# HoloCubicConnectV02_220109.net
KiCad netlist of a schematic drawn in Altium Designer
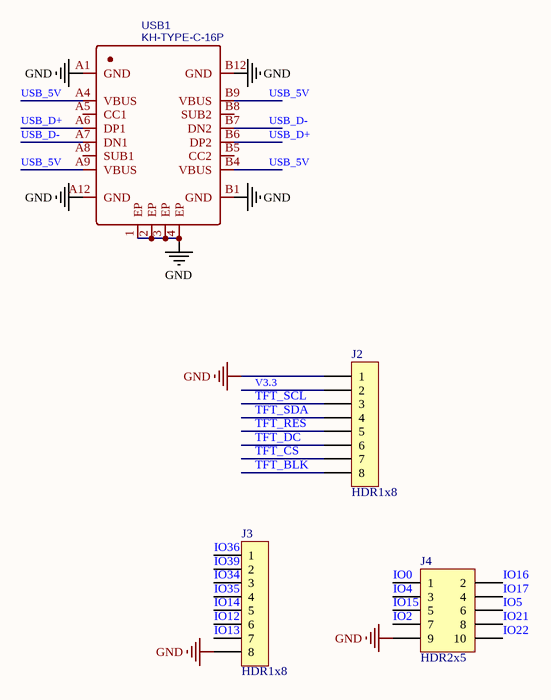
[diagram p0: HoloCubicConnectV02_220109.SchDoc]

(export (version "E")
  (design (tool "Eeschema 10.0.6"))
  (components
    (comp (ref "J2")
      (value "HDR1x8")
      (footprint "PIN-8-2.54-1.0")
      (description "Connector")
      (libsource (lib "General") (part "HDR1x8"))
    )
    (comp (ref "J3")
      (value "HDR1x8")
      (footprint "PIN-8-2.54-1.0")
      (description "Connector")
      (libsource (lib "General") (part "HDR1x8"))
    )
    (comp (ref "J4")
      (value "HDR2x5")
      (footprint "PIN-2x5-2.54-1.0")
      (description "Connector")
      (libsource (lib "General") (part "HDR2x5"))
    )
    (comp (ref "USB1")
      (value "KH-TYPE-C-16P")
      (footprint "USB-C-SMD_KH-TYPE-C-16P")
      (fields (field (name "BOM_SUPPLIER PART") "C709357") (field (name "CONTRIBUTOR") "LCSC"))
      (libsource (lib "altium-import") (part "root_0_KH-TYPE-C-16P_"))
    )
  )
  (nets
    (net (code "1") (name "/IO0") (class "Default")
      (node (ref "J4") (pin "1") (pinfunction "1_1") (pintype "passive"))
    )
    (net (code "2") (name "/IO2") (class "Default")
      (node (ref "J4") (pin "7") (pinfunction "7_7") (pintype "passive"))
    )
    (net (code "3") (name "/IO4") (class "Default")
      (node (ref "J4") (pin "3") (pinfunction "3_3") (pintype "passive"))
    )
    (net (code "4") (name "/IO5") (class "Default")
      (node (ref "J4") (pin "6") (pinfunction "6_6") (pintype "passive"))
    )
    (net (code "5") (name "/IO12") (class "Default")
      (node (ref "J3") (pin "6") (pinfunction "6_6") (pintype "passive"))
    )
    (net (code "6") (name "/IO13") (class "Default")
      (node (ref "J3") (pin "7") (pinfunction "7_7") (pintype "passive"))
    )
    (net (code "7") (name "/IO14") (class "Default")
      (node (ref "J3") (pin "5") (pinfunction "5_5") (pintype "passive"))
    )
    (net (code "8") (name "/IO15") (class "Default")
      (node (ref "J4") (pin "5") (pinfunction "5_5") (pintype "passive"))
    )
    (net (code "9") (name "/IO16") (class "Default")
      (node (ref "J4") (pin "2") (pinfunction "2_2") (pintype "passive"))
    )
    (net (code "10") (name "/IO17") (class "Default")
      (node (ref "J4") (pin "4") (pinfunction "4_4") (pintype "passive"))
    )
    (net (code "11") (name "/IO21") (class "Default")
      (node (ref "J4") (pin "8") (pinfunction "8_8") (pintype "passive"))
    )
    (net (code "12") (name "/IO22") (class "Default")
      (node (ref "J4") (pin "10") (pinfunction "10_10") (pintype "passive"))
    )
    (net (code "13") (name "/IO34") (class "Default")
      (node (ref "J3") (pin "3") (pinfunction "3_3") (pintype "passive"))
    )
    (net (code "14") (name "/IO35") (class "Default")
      (node (ref "J3") (pin "4") (pinfunction "4_4") (pintype "passive"))
    )
    (net (code "15") (name "/IO36") (class "Default")
      (node (ref "J3") (pin "1") (pinfunction "1_1") (pintype "passive"))
    )
    (net (code "16") (name "/IO39") (class "Default")
      (node (ref "J3") (pin "2") (pinfunction "2_2") (pintype "passive"))
    )
    (net (code "17") (name "/TFT_BLK") (class "Default")
      (node (ref "J2") (pin "8") (pinfunction "8_8") (pintype "passive"))
    )
    (net (code "18") (name "/TFT_CS") (class "Default")
      (node (ref "J2") (pin "7") (pinfunction "7_7") (pintype "passive"))
    )
    (net (code "19") (name "/TFT_DC") (class "Default")
      (node (ref "J2") (pin "6") (pinfunction "6_6") (pintype "passive"))
    )
    (net (code "20") (name "/TFT_RES") (class "Default")
      (node (ref "J2") (pin "5") (pinfunction "5_5") (pintype "passive"))
    )
    (net (code "21") (name "/TFT_SCL") (class "Default")
      (node (ref "J2") (pin "3") (pinfunction "3_3") (pintype "passive"))
    )
    (net (code "22") (name "/TFT_SDA") (class "Default")
      (node (ref "J2") (pin "4") (pinfunction "4_4") (pintype "passive"))
    )
    (net (code "23") (name "/USB_5V") (class "Default")
      (node (ref "USB1") (pin "A4") (pinfunction "VBUS_A4") (pintype "passive"))
      (node (ref "USB1") (pin "A9") (pinfunction "VBUS_A9") (pintype "passive"))
      (node (ref "USB1") (pin "B4") (pinfunction "VBUS_B4") (pintype "passive"))
      (node (ref "USB1") (pin "B9") (pinfunction "VBUS_B9") (pintype "passive"))
    )
    (net (code "24") (name "/USB_D+") (class "Default")
      (node (ref "USB1") (pin "A6") (pinfunction "DP1_A6") (pintype "passive"))
      (node (ref "USB1") (pin "B6") (pinfunction "DP2_B6") (pintype "passive"))
    )
    (net (code "25") (name "/USB_D-") (class "Default")
      (node (ref "USB1") (pin "A7") (pinfunction "DN1_A7") (pintype "passive"))
      (node (ref "USB1") (pin "B7") (pinfunction "DN2_B7") (pintype "passive"))
    )
    (net (code "26") (name "/V3.3") (class "Default")
      (node (ref "J2") (pin "2") (pinfunction "2_2") (pintype "passive"))
    )
    (net (code "27") (name "GND") (class "Default")
      (node (ref "J2") (pin "1") (pinfunction "1_1") (pintype "passive"))
      (node (ref "J3") (pin "8") (pinfunction "8_8") (pintype "passive"))
      (node (ref "J4") (pin "9") (pinfunction "9_9") (pintype "passive"))
      (node (ref "USB1") (pin "1") (pinfunction "EP_1") (pintype "passive"))
      (node (ref "USB1") (pin "2") (pinfunction "EP_2") (pintype "passive"))
      (node (ref "USB1") (pin "3") (pinfunction "EP_3") (pintype "passive"))
      (node (ref "USB1") (pin "4") (pinfunction "EP_4") (pintype "passive"))
      (node (ref "USB1") (pin "A1") (pinfunction "GND_A1") (pintype "passive"))
      (node (ref "USB1") (pin "A12") (pinfunction "GND_A12") (pintype "passive"))
      (node (ref "USB1") (pin "B1") (pinfunction "GND_B1") (pintype "passive"))
      (node (ref "USB1") (pin "B12") (pinfunction "GND_B12") (pintype "passive"))
    )
    (net (code "28") (name "unconnected-(USB1-CC1-PadA5)") (class "Default")
      (node (ref "USB1") (pin "A5") (pinfunction "CC1_A5") (pintype "passive"))
    )
    (net (code "29") (name "unconnected-(USB1-CC2-PadB5)") (class "Default")
      (node (ref "USB1") (pin "B5") (pinfunction "CC2_B5") (pintype "passive"))
    )
    (net (code "30") (name "unconnected-(USB1-SUB1-PadA8)") (class "Default")
      (node (ref "USB1") (pin "A8") (pinfunction "SUB1_A8") (pintype "passive"))
    )
    (net (code "31") (name "unconnected-(USB1-SUB2-PadB8)") (class "Default")
      (node (ref "USB1") (pin "B8") (pinfunction "SUB2_B8") (pintype "passive"))
    )
  )
)
